# schematic.net
KiCad netlist of a schematic drawn in EAGLE
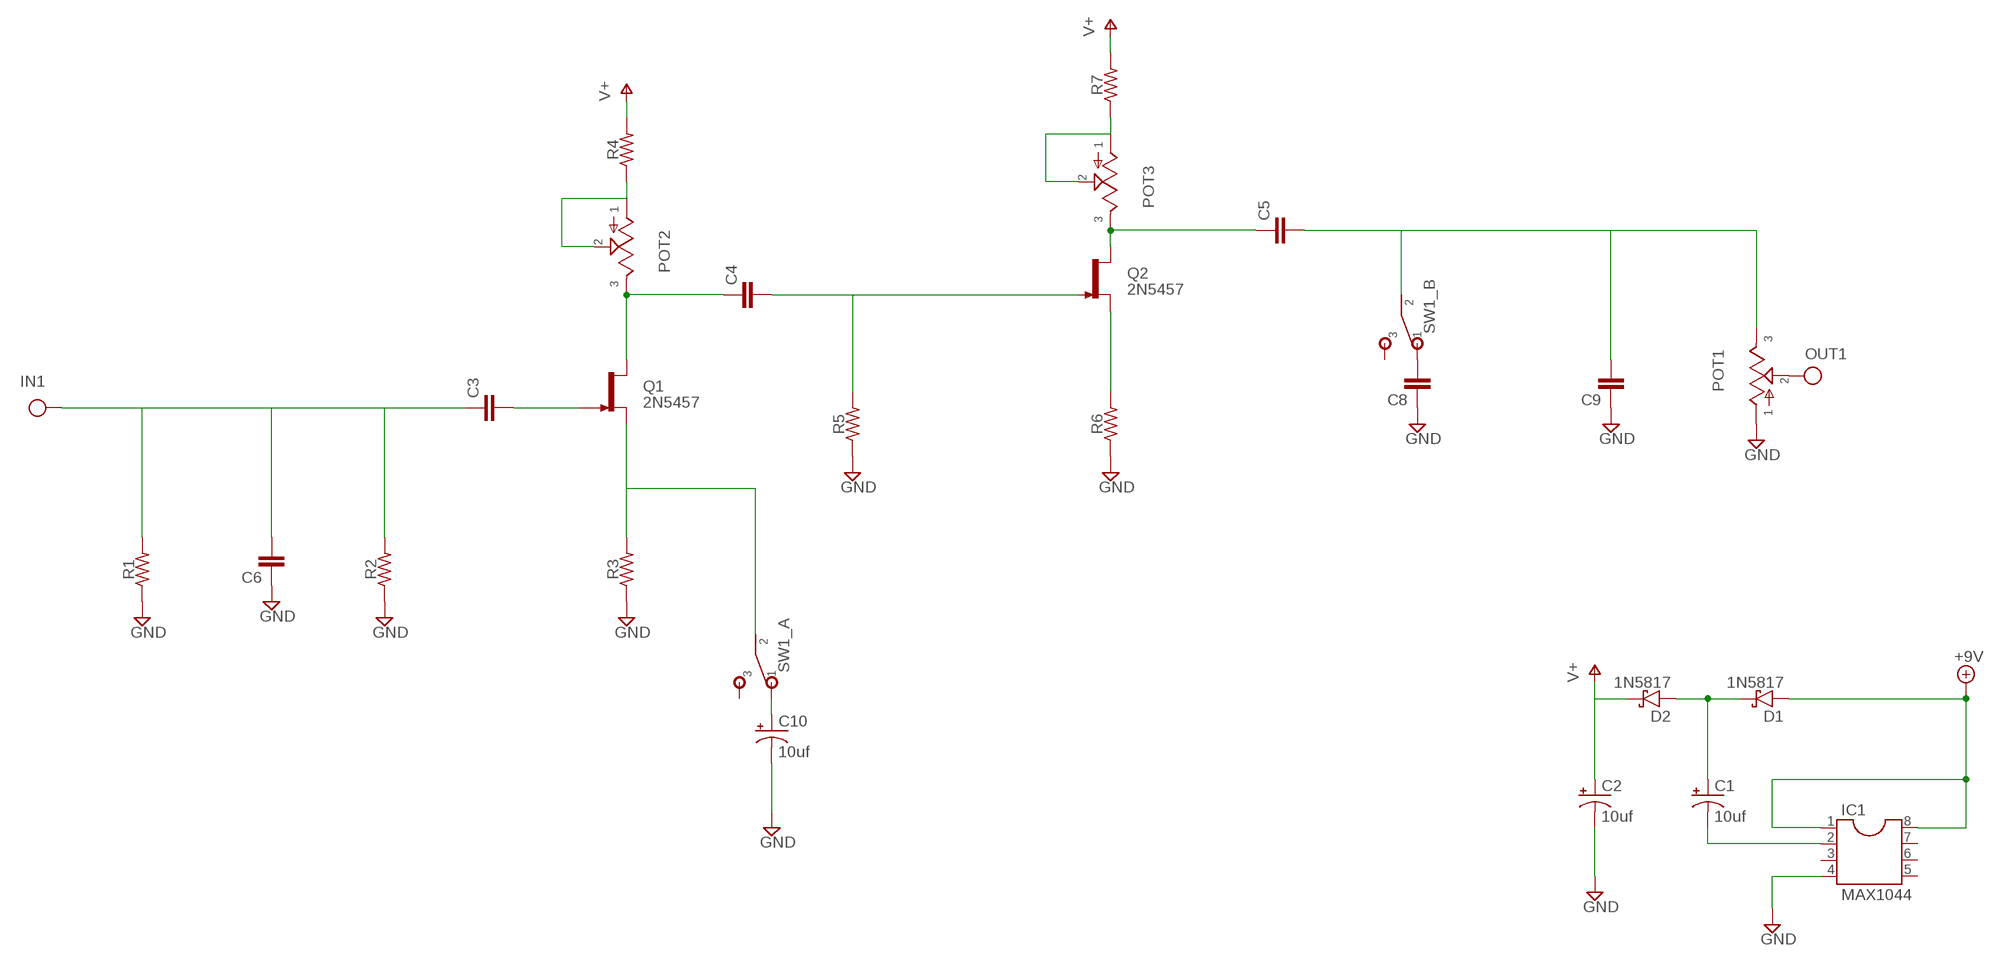
[diagram p0: schematic, sheet 1]

(export (version "E")
  (design (tool "Eeschema 10.0.6"))
  (components
    (comp (ref "C1")
      (value "10uf")
      (footprint "eagle-import:050_020_1")
      (libsource (lib "eagle-import") (part "0501"))
    )
    (comp (ref "C2")
      (value "10uf")
      (footprint "eagle-import:050_020_1")
      (libsource (lib "eagle-import") (part "0501"))
    )
    (comp (ref "C3")
      (value "072X0252")
      (footprint "eagle-import:072X025")
      (libsource (lib "eagle-import") (part "072X0252"))
    )
    (comp (ref "C4")
      (value "072X0252")
      (footprint "eagle-import:072X025")
      (libsource (lib "eagle-import") (part "072X0252"))
    )
    (comp (ref "C5")
      (value "072X0252")
      (footprint "eagle-import:072X025")
      (libsource (lib "eagle-import") (part "072X0252"))
    )
    (comp (ref "C6")
      (value "072X0252")
      (footprint "eagle-import:072X025")
      (libsource (lib "eagle-import") (part "072X0252"))
    )
    (comp (ref "C8")
      (value "072X0252")
      (footprint "eagle-import:072X025")
      (libsource (lib "eagle-import") (part "072X0252"))
    )
    (comp (ref "C9")
      (value "072X0252")
      (footprint "eagle-import:072X025")
      (libsource (lib "eagle-import") (part "072X0252"))
    )
    (comp (ref "C10")
      (value "10uf")
      (footprint "eagle-import:050_020_1")
      (libsource (lib "eagle-import") (part "0501"))
    )
    (comp (ref "D1")
      (value "1N5817")
      (footprint "eagle-import:DO41-3")
      (libsource (lib "eagle-import") (part "1N5817"))
    )
    (comp (ref "D2")
      (value "1N5817")
      (footprint "eagle-import:DO41-3")
      (libsource (lib "eagle-import") (part "1N5817"))
    )
    (comp (ref "IC1")
      (value "MAX1044")
      (footprint "eagle-import:DIL08")
      (libsource (lib "eagle-import") (part "MAX1044"))
    )
    (comp (ref "IN1")
      (value "IN(T)")
      (footprint "eagle-import:SQUARE")
      (libsource (lib "eagle-import") (part "IN(T)"))
    )
    (comp (ref "OUT1")
      (value "OUT(T)")
      (footprint "eagle-import:SQUARE")
      (libsource (lib "eagle-import") (part "OUT(T)"))
    )
    (comp (ref "POT1")
      (value "POT")
      (footprint "eagle-import:POT")
      (libsource (lib "eagle-import") (part "POT"))
    )
    (comp (ref "POT2")
      (value "POTTRIM")
      (footprint "eagle-import:B25P")
      (libsource (lib "eagle-import") (part "POTTRIM"))
    )
    (comp (ref "POT3")
      (value "POTTRIM")
      (footprint "eagle-import:B25P")
      (libsource (lib "eagle-import") (part "POTTRIM"))
    )
    (comp (ref "Q1")
      (value "2N5457")
      (footprint "eagle-import:TO92-")
      (libsource (lib "eagle-import") (part "2N5457"))
    )
    (comp (ref "Q2")
      (value "2N5457")
      (footprint "eagle-import:TO92-")
      (libsource (lib "eagle-import") (part "2N5457"))
    )
    (comp (ref "R1")
      (value "R.3B")
      (footprint "eagle-import:7.5MM.2")
      (libsource (lib "eagle-import") (part "R.3B"))
    )
    (comp (ref "R2")
      (value "R.3B")
      (footprint "eagle-import:7.5MM.2")
      (libsource (lib "eagle-import") (part "R.3B"))
    )
    (comp (ref "R3")
      (value "R.3B")
      (footprint "eagle-import:7.5MM.2")
      (libsource (lib "eagle-import") (part "R.3B"))
    )
    (comp (ref "R4")
      (value "R.3B")
      (footprint "eagle-import:7.5MM.2")
      (libsource (lib "eagle-import") (part "R.3B"))
    )
    (comp (ref "R5")
      (value "R.3B")
      (footprint "eagle-import:7.5MM.2")
      (libsource (lib "eagle-import") (part "R.3B"))
    )
    (comp (ref "R6")
      (value "R.3B")
      (footprint "eagle-import:7.5MM.2")
      (libsource (lib "eagle-import") (part "R.3B"))
    )
    (comp (ref "R7")
      (value "R.3B")
      (footprint "eagle-import:7.5MM.2")
      (libsource (lib "eagle-import") (part "R.3B"))
    )
    (comp (ref "SW1")
      (value "DPDT.1")
      (footprint "eagle-import:DPDT_SOLDER_LUG")
      (libsource (lib "eagle-import") (part "DPDT.1"))
    )
  )
  (nets
    (net (code "1") (name "+9V") (class "Default")
      (node (ref "D1") (pin "A") (pinfunction "A_A") (pintype "passive"))
      (node (ref "IC1") (pin "1") (pinfunction "1_1") (pintype "passive"))
      (node (ref "IC1") (pin "8") (pinfunction "8_8") (pintype "passive"))
    )
    (net (code "2") (name "GND") (class "Default")
      (node (ref "C10") (pin "-") (pinfunction "-_-") (pintype "passive"))
      (node (ref "C2") (pin "-") (pinfunction "-_-") (pintype "passive"))
      (node (ref "C6") (pin "1") (pinfunction "1_1") (pintype "passive"))
      (node (ref "C8") (pin "1") (pinfunction "1_1") (pintype "passive"))
      (node (ref "C9") (pin "1") (pinfunction "1_1") (pintype "passive"))
      (node (ref "IC1") (pin "4") (pinfunction "4_4") (pintype "passive"))
      (node (ref "POT1") (pin "1") (pinfunction "1_1") (pintype "passive"))
      (node (ref "R1") (pin "1") (pinfunction "1_1") (pintype "passive"))
      (node (ref "R2") (pin "1") (pinfunction "1_1") (pintype "passive"))
      (node (ref "R3") (pin "1") (pinfunction "1_1") (pintype "passive"))
      (node (ref "R5") (pin "1") (pinfunction "1_1") (pintype "passive"))
      (node (ref "R6") (pin "1") (pinfunction "1_1") (pintype "passive"))
    )
    (net (code "3") (name "IN(T)") (class "Default")
      (node (ref "C3") (pin "1") (pinfunction "1_1") (pintype "passive"))
      (node (ref "C6") (pin "2") (pinfunction "2_2") (pintype "passive"))
      (node (ref "IN1") (pin "1") (pinfunction "IN_1") (pintype "power_in"))
      (node (ref "R1") (pin "2") (pinfunction "2_2") (pintype "passive"))
      (node (ref "R2") (pin "2") (pinfunction "2_2") (pintype "passive"))
    )
    (net (code "4") (name "Net-(C1-Pad+)") (class "Default")
      (node (ref "C1") (pin "+") (pinfunction "+_+") (pintype "passive"))
      (node (ref "D1") (pin "C") (pinfunction "C_C") (pintype "passive"))
      (node (ref "D2") (pin "A") (pinfunction "A_A") (pintype "passive"))
    )
    (net (code "5") (name "Net-(C1-Pad-)") (class "Default")
      (node (ref "C1") (pin "-") (pinfunction "-_-") (pintype "passive"))
      (node (ref "IC1") (pin "2") (pinfunction "2_2") (pintype "passive"))
    )
    (net (code "6") (name "Net-(C4-Pad2)") (class "Default")
      (node (ref "C4") (pin "2") (pinfunction "2_2") (pintype "passive"))
      (node (ref "R5") (pin "2") (pinfunction "2_2") (pintype "passive"))
    )
    (net (code "7") (name "Net-(POT2-Pad1)") (class "Default")
      (node (ref "POT2") (pin "1") (pinfunction "1_1") (pintype "passive"))
      (node (ref "POT2") (pin "2") (pinfunction "2_2") (pintype "passive"))
      (node (ref "R4") (pin "1") (pinfunction "1_1") (pintype "passive"))
    )
    (net (code "8") (name "Net-(POT3-Pad1)") (class "Default")
      (node (ref "POT3") (pin "1") (pinfunction "1_1") (pintype "passive"))
      (node (ref "POT3") (pin "2") (pinfunction "2_2") (pintype "passive"))
      (node (ref "R7") (pin "1") (pinfunction "1_1") (pintype "passive"))
    )
    (net (code "9") (name "Net-(Q1-D)") (class "Default")
      (node (ref "C4") (pin "1") (pinfunction "1_1") (pintype "passive"))
      (node (ref "POT2") (pin "3") (pinfunction "3_3") (pintype "passive"))
      (node (ref "Q1") (pin "3") (pinfunction "D_3") (pintype "passive"))
    )
    (net (code "10") (name "Net-(Q1-G)") (class "Default")
      (node (ref "C3") (pin "2") (pinfunction "2_2") (pintype "passive"))
      (node (ref "Q1") (pin "1") (pinfunction "G_1") (pintype "passive"))
    )
    (net (code "11") (name "Net-(Q1-S)") (class "Default")
      (node (ref "Q1") (pin "2") (pinfunction "S_2") (pintype "passive"))
      (node (ref "R3") (pin "2") (pinfunction "2_2") (pintype "passive"))
      (node (ref "SW1") (pin "A2") (pinfunction "2_A2") (pintype "passive"))
    )
    (net (code "12") (name "Net-(Q2-D)") (class "Default")
      (node (ref "C5") (pin "1") (pinfunction "1_1") (pintype "passive"))
      (node (ref "POT3") (pin "3") (pinfunction "3_3") (pintype "passive"))
      (node (ref "Q2") (pin "3") (pinfunction "D_3") (pintype "passive"))
    )
    (net (code "13") (name "Net-(Q2-S)") (class "Default")
      (node (ref "Q2") (pin "2") (pinfunction "S_2") (pintype "passive"))
      (node (ref "R6") (pin "2") (pinfunction "2_2") (pintype "passive"))
    )
    (net (code "14") (name "Net-(SW1A-1)") (class "Default")
      (node (ref "C10") (pin "+") (pinfunction "+_+") (pintype "passive"))
      (node (ref "SW1") (pin "A1") (pinfunction "1_A1") (pintype "passive"))
    )
    (net (code "15") (name "Net-(SW1B-1)") (class "Default")
      (node (ref "C8") (pin "2") (pinfunction "2_2") (pintype "passive"))
      (node (ref "SW1") (pin "B1") (pinfunction "1_B1") (pintype "passive"))
    )
    (net (code "16") (name "Net-(SW1B-2)") (class "Default")
      (node (ref "C5") (pin "2") (pinfunction "2_2") (pintype "passive"))
      (node (ref "C9") (pin "2") (pinfunction "2_2") (pintype "passive"))
      (node (ref "POT1") (pin "3") (pinfunction "3_3") (pintype "passive"))
      (node (ref "SW1") (pin "B2") (pinfunction "2_B2") (pintype "passive"))
    )
    (net (code "17") (name "OUT(T)") (class "Default")
      (node (ref "OUT1") (pin "1") (pinfunction "OUT_1") (pintype "power_in"))
      (node (ref "POT1") (pin "2") (pinfunction "2_2") (pintype "passive"))
    )
    (net (code "18") (name "V+") (class "Default")
      (node (ref "C2") (pin "+") (pinfunction "+_+") (pintype "passive"))
      (node (ref "D2") (pin "C") (pinfunction "C_C") (pintype "passive"))
      (node (ref "R4") (pin "2") (pinfunction "2_2") (pintype "passive"))
      (node (ref "R7") (pin "2") (pinfunction "2_2") (pintype "passive"))
    )
    (net (code "19") (name "unconnected-(IC1-Pad3)") (class "Default")
      (node (ref "IC1") (pin "3") (pinfunction "3_3") (pintype "passive"))
    )
    (net (code "20") (name "unconnected-(IC1-Pad5)") (class "Default")
      (node (ref "IC1") (pin "5") (pinfunction "5_5") (pintype "passive"))
    )
    (net (code "21") (name "unconnected-(IC1-Pad6)") (class "Default")
      (node (ref "IC1") (pin "6") (pinfunction "6_6") (pintype "passive"))
    )
    (net (code "22") (name "unconnected-(IC1-Pad7)") (class "Default")
      (node (ref "IC1") (pin "7") (pinfunction "7_7") (pintype "passive"))
    )
    (net (code "23") (name "unconnected-(Q2-G-Pad1)") (class "Default")
      (node (ref "Q2") (pin "1") (pinfunction "G_1") (pintype "passive"))
    )
    (net (code "24") (name "unconnected-(SW1A-3-PadA3)") (class "Default")
      (node (ref "SW1") (pin "A3") (pinfunction "3_A3") (pintype "passive"))
    )
    (net (code "25") (name "unconnected-(SW1B-3-PadB3)") (class "Default")
      (node (ref "SW1") (pin "B3") (pinfunction "3_B3") (pintype "passive"))
    )
  )
)
